# System_Schem_2020-06-05_15-55-24.net
KiCad netlist of a schematic drawn in EasyEDA
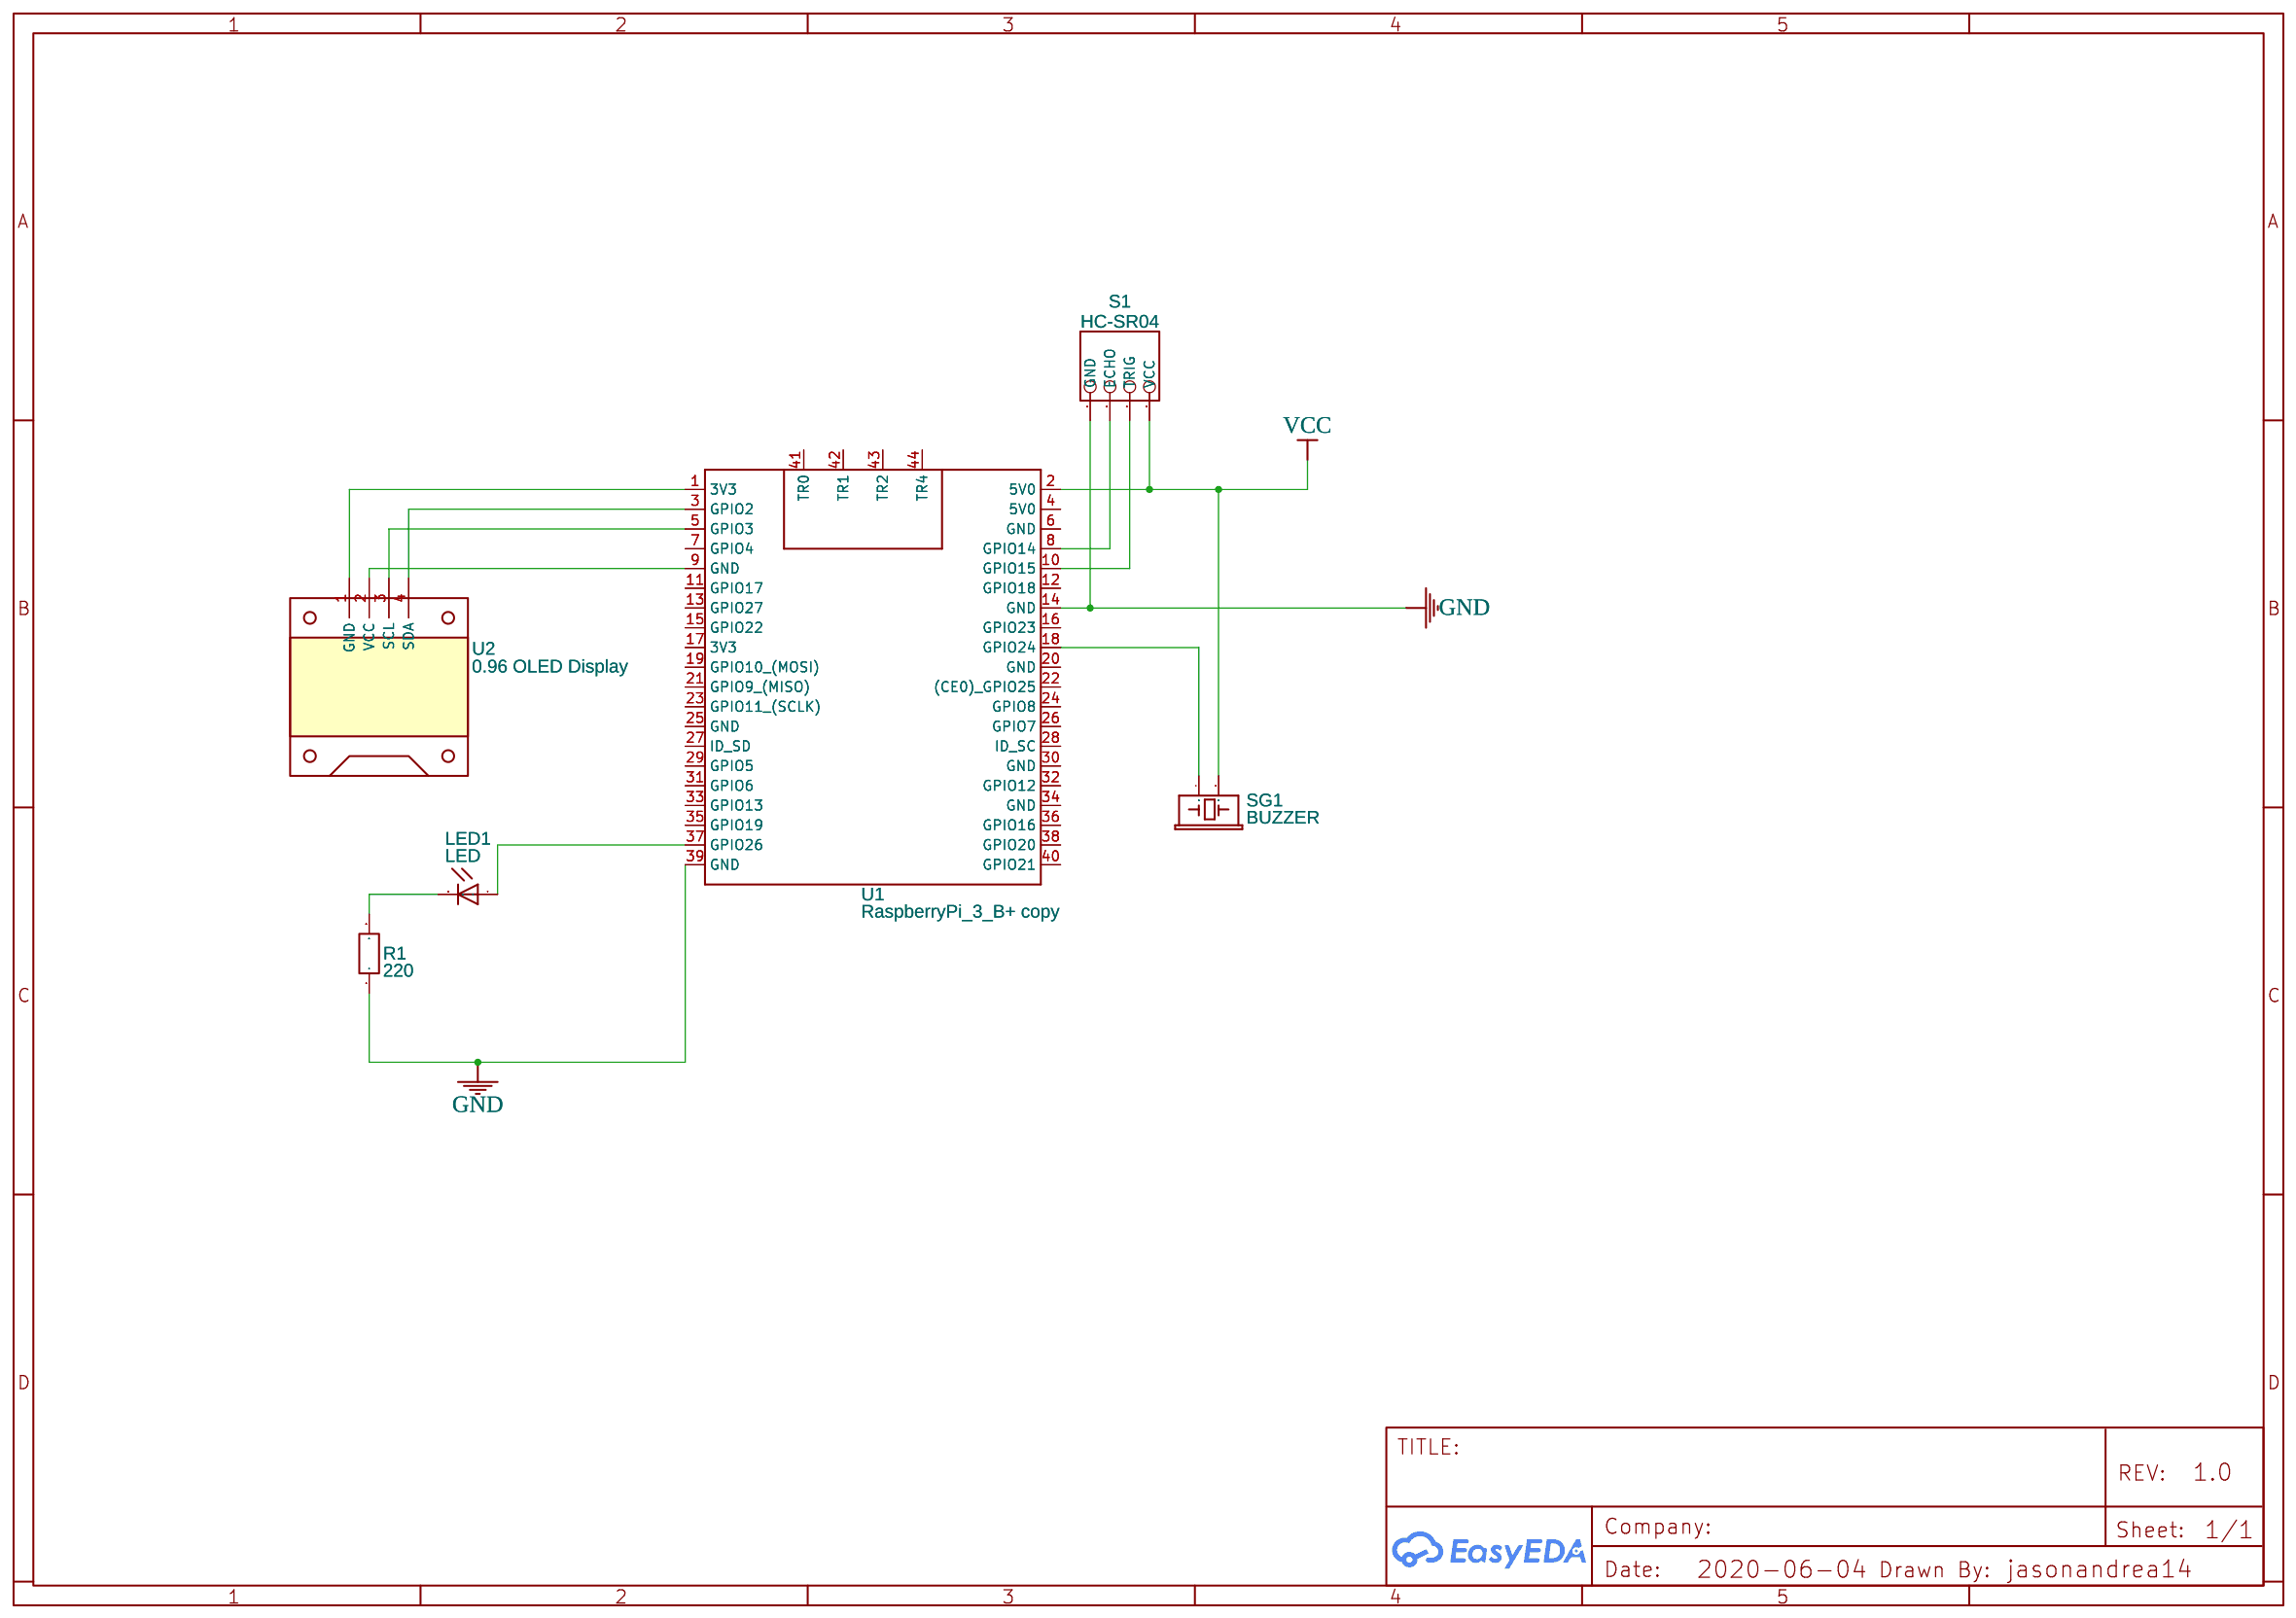
[diagram p0: schematic sheet]

(export (version "E")
  (design (tool "Eeschema 10.0.6"))
  (components
    (comp (ref "LED1") (value "LED") (libsource (lib "") (part "LED")))
    (comp (ref "R1") (value "220") (libsource (lib "") (part "R_0201_EU")))
    (comp (ref "S1") (value "HC-SR04") (libsource (lib "") (part "HC-SR04")))
    (comp (ref "SG1") (value "BUZZER") (libsource (lib "") (part "BUZZER")))
    (comp (ref "U1")
      (value "RaspberryPi_3_B+ copy")
      (fields (field (name "BOM_Manufacturer Part") "RaspberryPi 3"))
      (libsource (lib "") (part "RaspberryPi_3_B+ copy"))
    )
    (comp (ref "U2")
      (value "0.96 OLED Display")
      (fields (field (name "BOM_Manufacturer Part") "0.96 OLED"))
      (libsource (lib "") (part "0.96 OLED Display"))
    )
  )
  (nets
    (net (code "1") (name "GND") (class "Default")
      (node (ref "R1") (pin "1") (pinfunction "1_1") (pintype "unspecified"))
      (node (ref "S1") (pin "4") (pinfunction "GND_4") (pintype "unspecified"))
      (node (ref "U1") (pin "14") (pinfunction "GND_14") (pintype "unspecified"))
      (node (ref "U1") (pin "39") (pinfunction "GND_39") (pintype "unspecified"))
    )
    (net (code "2") (name "Net-(LED1-PadC)") (class "Default")
      (node (ref "LED1") (pin "C") (pinfunction "C_C") (pintype "unspecified"))
      (node (ref "R1") (pin "2") (pinfunction "2_2") (pintype "unspecified"))
    )
    (net (code "3") (name "Net-(S1-ECHO)") (class "Default")
      (node (ref "S1") (pin "3") (pinfunction "ECHO_3") (pintype "unspecified"))
      (node (ref "U1") (pin "8") (pinfunction "GPIO14_8") (pintype "unspecified"))
    )
    (net (code "4") (name "Net-(S1-TRIG)") (class "Default")
      (node (ref "S1") (pin "2") (pinfunction "TRIG_2") (pintype "unspecified"))
      (node (ref "U1") (pin "10") (pinfunction "GPIO15_10") (pintype "unspecified"))
    )
    (net (code "5") (name "Net-(SG1-2)") (class "Default")
      (node (ref "SG1") (pin "-") (pinfunction "2_-") (pintype "unspecified"))
      (node (ref "U1") (pin "18") (pinfunction "GPIO24_18") (pintype "unspecified"))
    )
    (net (code "6") (name "Net-(U1-GPIO2)") (class "Default")
      (node (ref "U1") (pin "3") (pinfunction "GPIO2_3") (pintype "unspecified"))
      (node (ref "U2") (pin "4") (pinfunction "SDA_4") (pintype "unspecified"))
    )
    (net (code "7") (name "Net-(U1-GPIO3)") (class "Default")
      (node (ref "U1") (pin "5") (pinfunction "GPIO3_5") (pintype "unspecified"))
      (node (ref "U2") (pin "3") (pinfunction "SCL_3") (pintype "unspecified"))
    )
    (net (code "8") (name "Net-(U1-GPIO26)") (class "Default")
      (node (ref "LED1") (pin "A") (pinfunction "A_A") (pintype "unspecified"))
      (node (ref "U1") (pin "37") (pinfunction "GPIO26_37") (pintype "unspecified"))
    )
    (net (code "9") (name "Net-(U2-GND)") (class "Default")
      (node (ref "U1") (pin "1") (pinfunction "3V3_1") (pintype "unspecified"))
      (node (ref "U2") (pin "1") (pinfunction "GND_1") (pintype "unspecified"))
    )
    (net (code "10") (name "Net-(U2-VCC)") (class "Default")
      (node (ref "U1") (pin "9") (pinfunction "GND_9") (pintype "unspecified"))
      (node (ref "U2") (pin "2") (pinfunction "VCC_2") (pintype "unspecified"))
    )
    (net (code "11") (name "VCC") (class "Default")
      (node (ref "S1") (pin "1") (pinfunction "VCC_1") (pintype "unspecified"))
      (node (ref "SG1") (pin "+") (pinfunction "1_+") (pintype "unspecified"))
      (node (ref "U1") (pin "2") (pinfunction "5V0_2") (pintype "unspecified"))
    )
    (net (code "12") (name "unconnected-(U1-(CE0)_GPIO25-Pad22)") (class "Default")
      (node (ref "U1") (pin "22") (pinfunction "(CE0)_GPIO25_22") (pintype "unspecified"))
    )
    (net (code "13") (name "unconnected-(U1-3V3-Pad17)") (class "Default")
      (node (ref "U1") (pin "17") (pinfunction "3V3_17") (pintype "unspecified"))
    )
    (net (code "14") (name "unconnected-(U1-5V0-Pad4)") (class "Default")
      (node (ref "U1") (pin "4") (pinfunction "5V0_4") (pintype "unspecified"))
    )
    (net (code "15") (name "unconnected-(U1-GND-Pad6)") (class "Default")
      (node (ref "U1") (pin "6") (pinfunction "GND_6") (pintype "unspecified"))
    )
    (net (code "16") (name "unconnected-(U1-GND-Pad20)") (class "Default")
      (node (ref "U1") (pin "20") (pinfunction "GND_20") (pintype "unspecified"))
    )
    (net (code "17") (name "unconnected-(U1-GND-Pad25)") (class "Default")
      (node (ref "U1") (pin "25") (pinfunction "GND_25") (pintype "unspecified"))
    )
    (net (code "18") (name "unconnected-(U1-GND-Pad30)") (class "Default")
      (node (ref "U1") (pin "30") (pinfunction "GND_30") (pintype "unspecified"))
    )
    (net (code "19") (name "unconnected-(U1-GND-Pad34)") (class "Default")
      (node (ref "U1") (pin "34") (pinfunction "GND_34") (pintype "unspecified"))
    )
    (net (code "20") (name "unconnected-(U1-GPIO4-Pad7)") (class "Default")
      (node (ref "U1") (pin "7") (pinfunction "GPIO4_7") (pintype "unspecified"))
    )
    (net (code "21") (name "unconnected-(U1-GPIO5-Pad29)") (class "Default")
      (node (ref "U1") (pin "29") (pinfunction "GPIO5_29") (pintype "unspecified"))
    )
    (net (code "22") (name "unconnected-(U1-GPIO6-Pad31)") (class "Default")
      (node (ref "U1") (pin "31") (pinfunction "GPIO6_31") (pintype "unspecified"))
    )
    (net (code "23") (name "unconnected-(U1-GPIO7-Pad26)") (class "Default")
      (node (ref "U1") (pin "26") (pinfunction "GPIO7_26") (pintype "unspecified"))
    )
    (net (code "24") (name "unconnected-(U1-GPIO8-Pad24)") (class "Default")
      (node (ref "U1") (pin "24") (pinfunction "GPIO8_24") (pintype "unspecified"))
    )
    (net (code "25") (name "unconnected-(U1-GPIO9_(MISO)-Pad21)") (class "Default")
      (node (ref "U1") (pin "21") (pinfunction "GPIO9_(MISO)_21") (pintype "unspecified"))
    )
    (net (code "26") (name "unconnected-(U1-GPIO10_(MOSI)-Pad19)") (class "Default")
      (node (ref "U1") (pin "19") (pinfunction "GPIO10_(MOSI)_19") (pintype "unspecified"))
    )
    (net (code "27") (name "unconnected-(U1-GPIO11_(SCLK)-Pad23)") (class "Default")
      (node (ref "U1") (pin "23") (pinfunction "GPIO11_(SCLK)_23") (pintype "unspecified"))
    )
    (net (code "28") (name "unconnected-(U1-GPIO12-Pad32)") (class "Default")
      (node (ref "U1") (pin "32") (pinfunction "GPIO12_32") (pintype "unspecified"))
    )
    (net (code "29") (name "unconnected-(U1-GPIO13-Pad33)") (class "Default")
      (node (ref "U1") (pin "33") (pinfunction "GPIO13_33") (pintype "unspecified"))
    )
    (net (code "30") (name "unconnected-(U1-GPIO16-Pad36)") (class "Default")
      (node (ref "U1") (pin "36") (pinfunction "GPIO16_36") (pintype "unspecified"))
    )
    (net (code "31") (name "unconnected-(U1-GPIO17-Pad11)") (class "Default")
      (node (ref "U1") (pin "11") (pinfunction "GPIO17_11") (pintype "unspecified"))
    )
    (net (code "32") (name "unconnected-(U1-GPIO18-Pad12)") (class "Default")
      (node (ref "U1") (pin "12") (pinfunction "GPIO18_12") (pintype "unspecified"))
    )
    (net (code "33") (name "unconnected-(U1-GPIO19-Pad35)") (class "Default")
      (node (ref "U1") (pin "35") (pinfunction "GPIO19_35") (pintype "unspecified"))
    )
    (net (code "34") (name "unconnected-(U1-GPIO20-Pad38)") (class "Default")
      (node (ref "U1") (pin "38") (pinfunction "GPIO20_38") (pintype "unspecified"))
    )
    (net (code "35") (name "unconnected-(U1-GPIO21-Pad40)") (class "Default")
      (node (ref "U1") (pin "40") (pinfunction "GPIO21_40") (pintype "unspecified"))
    )
    (net (code "36") (name "unconnected-(U1-GPIO22-Pad15)") (class "Default")
      (node (ref "U1") (pin "15") (pinfunction "GPIO22_15") (pintype "unspecified"))
    )
    (net (code "37") (name "unconnected-(U1-GPIO23-Pad16)") (class "Default")
      (node (ref "U1") (pin "16") (pinfunction "GPIO23_16") (pintype "unspecified"))
    )
    (net (code "38") (name "unconnected-(U1-GPIO27-Pad13)") (class "Default")
      (node (ref "U1") (pin "13") (pinfunction "GPIO27_13") (pintype "unspecified"))
    )
    (net (code "39") (name "unconnected-(U1-ID_SC-Pad28)") (class "Default")
      (node (ref "U1") (pin "28") (pinfunction "ID_SC_28") (pintype "unspecified"))
    )
    (net (code "40") (name "unconnected-(U1-ID_SD-Pad27)") (class "Default")
      (node (ref "U1") (pin "27") (pinfunction "ID_SD_27") (pintype "unspecified"))
    )
    (net (code "41") (name "unconnected-(U1-TR0-Pad41)") (class "Default")
      (node (ref "U1") (pin "41") (pinfunction "TR0_41") (pintype "unspecified"))
    )
    (net (code "42") (name "unconnected-(U1-TR1-Pad42)") (class "Default")
      (node (ref "U1") (pin "42") (pinfunction "TR1_42") (pintype "unspecified"))
    )
    (net (code "43") (name "unconnected-(U1-TR2-Pad43)") (class "Default")
      (node (ref "U1") (pin "43") (pinfunction "TR2_43") (pintype "unspecified"))
    )
    (net (code "44") (name "unconnected-(U1-TR4-Pad44)") (class "Default")
      (node (ref "U1") (pin "44") (pinfunction "TR4_44") (pintype "unspecified"))
    )
  )
)
